# Sensor_de_temperatura.net
KiCad netlist of a schematic drawn in Altium Designer
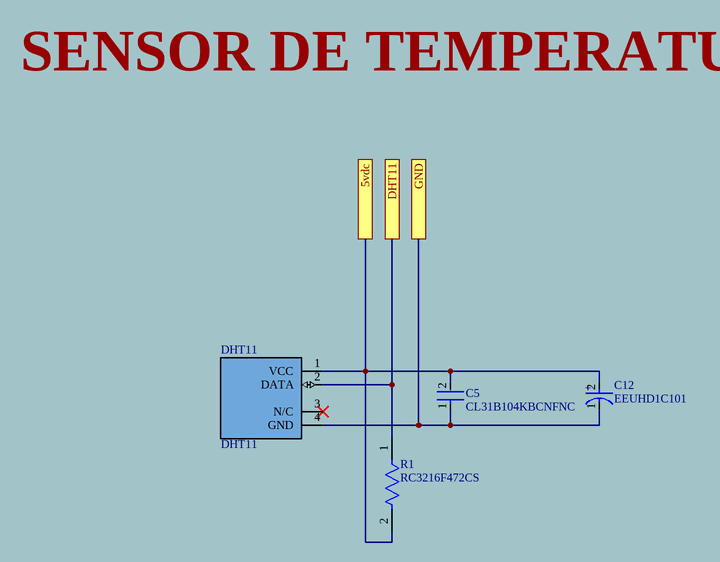
[diagram p0: Sensor de temperatura.SchDoc]

(export (version "E")
  (design (tool "Eeschema 10.0.6"))
  (components
    (comp (ref "C5")
      (value "CL31B104KBCNFNC")
      (footprint "FP-CL31-IPC_C")
      (description "Cap Ceramic 100nF 50V X7R ±10% SMD 1206 +125°C Embossed T/R")
      (fields (field (name "TOLERANCE") "10%"))
      (libsource (lib "Altium Content Vault") (part "b4654b650e69147ec39a6b967a45e02"))
    )
    (comp (ref "C12")
      (value "EEUHD1C101")
      (footprint "FP-RAD-TH-D_5_0_5-L_11_1-MFG")
      (description "Aluminum Electrolytic Capacitors (Radial Lead Type) AEC-Q200 Qualified 100uF ±20% 16V")
      (fields (field (name "TOLERANCE") "20%") (field (name "VOLTAGE") "16V"))
      (libsource (lib "Altium Content Vault") (part "a00bbbee19879c290e62620ae7e47b1"))
    )
    (comp (ref "DHT11")
      (value "DHT11")
      (footprint "DHT11")
      (description "SENSOR DE TEMPERATURA")
      (libsource (lib "DHT11") (part "DHT11"))
    )
    (comp (ref "R1")
      (value "RC3216F472CS")
      (footprint "FP-RC3216-MFG")
      (description "Res Thick Film 1206 4.7kΩ 1% 0.25W ±100ppm/°C Molded SMD T/R")
      (fields (field (name "TOLERANCE") "1%"))
      (libsource (lib "Altium Content Vault") (part "1029c3af85768c4190bb7ad29bc67b5"))
    )
  )
  (nets
    (net (code "1") (name "/5vdc") (class "Default")
      (node (ref "C12") (pin "2") (pinfunction "A_2") (pintype "passive"))
      (node (ref "C5") (pin "2") (pinfunction "2_2") (pintype "passive"))
      (node (ref "DHT11") (pin "1") (pinfunction "VCC_1") (pintype "power_in"))
      (node (ref "R1") (pin "2") (pinfunction "2_2") (pintype "passive"))
    )
    (net (code "2") (name "/DHT11") (class "Default")
      (node (ref "DHT11") (pin "2") (pinfunction "DATA_2") (pintype "bidirectional"))
      (node (ref "R1") (pin "1") (pinfunction "1_1") (pintype "passive"))
    )
    (net (code "3") (name "/GND") (class "Default")
      (node (ref "C12") (pin "1") (pinfunction "C_1") (pintype "passive"))
      (node (ref "C5") (pin "1") (pinfunction "1_1") (pintype "passive"))
      (node (ref "DHT11") (pin "4") (pinfunction "GND_4") (pintype "power_in"))
    )
    (net (code "4") (name "unconnected-(DHT11-N{slash}C-Pad3)") (class "Default")
      (node (ref "DHT11") (pin "3") (pinfunction "N/C_3") (pintype "passive+no_connect"))
    )
  )
)
